# 5VAC-DC_Atmega.net
KiCad netlist of a schematic drawn in EAGLE
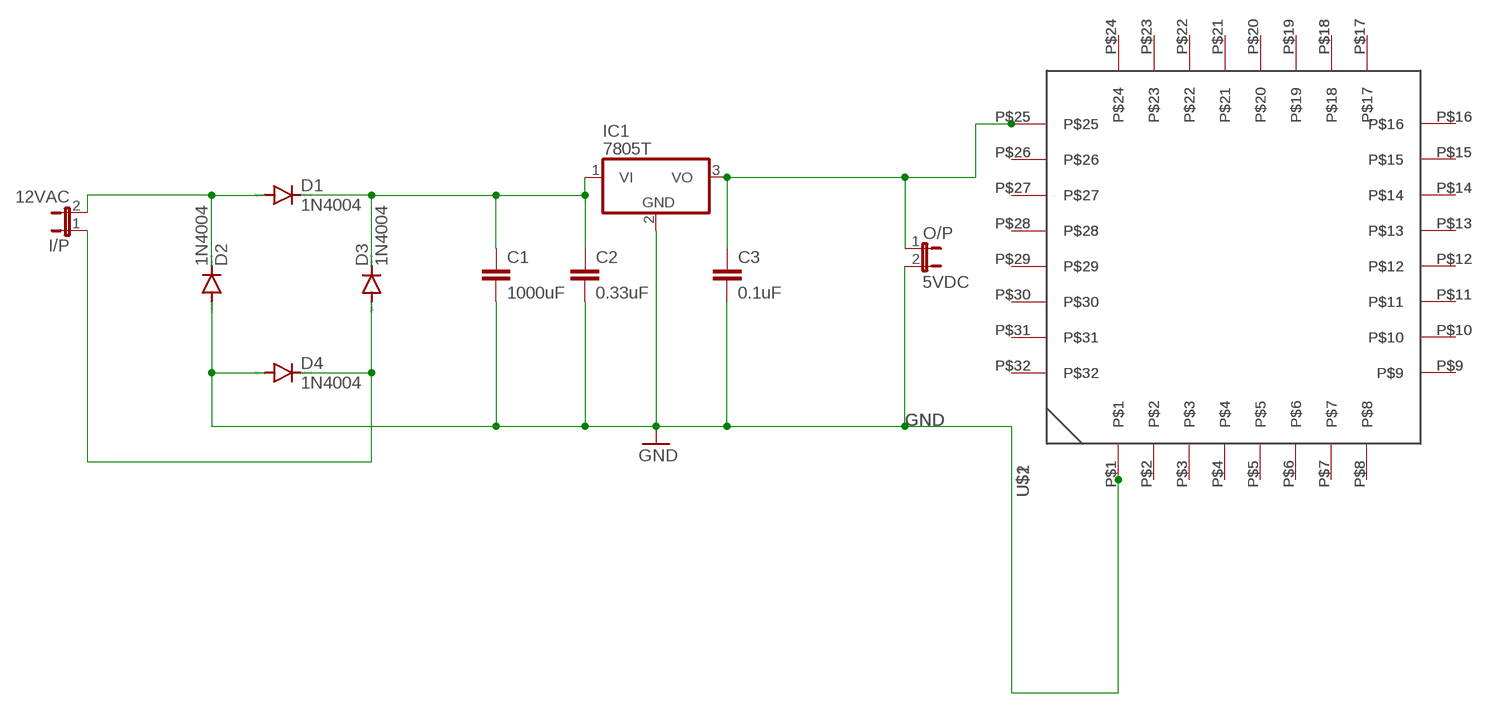
[diagram p0: schematic, sheet 1]

(export (version "E")
  (design (tool "Eeschema 10.0.6"))
  (components
    (comp (ref "C1")
      (value "1000uF")
      (footprint "eagle-import:C2.5-3")
      (libsource (lib "eagle-import") (part "C2,5-3"))
    )
    (comp (ref "C2")
      (value "0.33uF")
      (footprint "eagle-import:C2.5-3")
      (libsource (lib "eagle-import") (part "C2,5-3"))
    )
    (comp (ref "C3")
      (value "0.1uF")
      (footprint "eagle-import:C2.5-3")
      (libsource (lib "eagle-import") (part "C2,5-3"))
    )
    (comp (ref "D1")
      (value "1N4004")
      (footprint "eagle-import:DO41-10")
      (libsource (lib "eagle-import") (part "1N4004"))
    )
    (comp (ref "D2")
      (value "1N4004")
      (footprint "eagle-import:DO41-10")
      (libsource (lib "eagle-import") (part "1N4004"))
    )
    (comp (ref "D3")
      (value "1N4004")
      (footprint "eagle-import:DO41-10")
      (libsource (lib "eagle-import") (part "1N4004"))
    )
    (comp (ref "D4")
      (value "1N4004")
      (footprint "eagle-import:DO41-10")
      (libsource (lib "eagle-import") (part "1N4004"))
    )
    (comp (ref "I/P")
      (value "12VAC")
      (footprint "eagle-import:JP1")
      (libsource (lib "eagle-import") (part "JP1E"))
    )
    (comp (ref "IC1")
      (value "7805T")
      (footprint "eagle-import:TO220H")
      (libsource (lib "eagle-import") (part "78T05"))
    )
    (comp (ref "O/P")
      (value "5VDC")
      (footprint "eagle-import:JP1")
      (libsource (lib "eagle-import") (part "JP1E"))
    )
    (comp (ref "U$1")
      (value "MEGA8L-DEV")
      (footprint "eagle-import:TQFP-MEGA8L")
      (libsource (lib "eagle-import") (part "MEGA8L-DEV"))
    )
    (comp (ref "U$2")
      (value "MEGA8L-DEV")
      (footprint "eagle-import:TQFP-MEGA8L")
      (libsource (lib "eagle-import") (part "MEGA8L-DEV"))
    )
  )
  (nets
    (net (code "1") (name "GND") (class "Default")
      (node (ref "C1") (pin "2") (pinfunction "2_2") (pintype "passive"))
      (node (ref "C2") (pin "2") (pinfunction "2_2") (pintype "passive"))
      (node (ref "C3") (pin "2") (pinfunction "2_2") (pintype "passive"))
      (node (ref "D2") (pin "A") (pinfunction "A_A") (pintype "passive"))
      (node (ref "D4") (pin "A") (pinfunction "A_A") (pintype "passive"))
      (node (ref "IC1") (pin "2") (pinfunction "GND_2") (pintype "passive"))
      (node (ref "O/P") (pin "2") (pinfunction "2_2") (pintype "passive"))
      (node (ref "U$1") (pin "P$1") (pinfunction "P$1_P$1") (pintype "bidirectional"))
      (node (ref "U$2") (pin "P$1") (pinfunction "P$1_P$1") (pintype "bidirectional"))
    )
    (net (code "2") (name "Net-(D1-PadA)") (class "Default")
      (node (ref "D1") (pin "A") (pinfunction "A_A") (pintype "passive"))
      (node (ref "D2") (pin "C") (pinfunction "C_C") (pintype "passive"))
      (node (ref "I/P") (pin "2") (pinfunction "2_2") (pintype "passive"))
    )
    (net (code "3") (name "Net-(D3-PadA)") (class "Default")
      (node (ref "D3") (pin "A") (pinfunction "A_A") (pintype "passive"))
      (node (ref "D4") (pin "C") (pinfunction "C_C") (pintype "passive"))
      (node (ref "I/P") (pin "1") (pinfunction "1_1") (pintype "passive"))
    )
    (net (code "4") (name "Net-(IC1-VI)") (class "Default")
      (node (ref "C1") (pin "1") (pinfunction "1_1") (pintype "passive"))
      (node (ref "C2") (pin "1") (pinfunction "1_1") (pintype "passive"))
      (node (ref "D1") (pin "C") (pinfunction "C_C") (pintype "passive"))
      (node (ref "D3") (pin "C") (pinfunction "C_C") (pintype "passive"))
      (node (ref "IC1") (pin "1") (pinfunction "VI_1") (pintype "input"))
    )
    (net (code "5") (name "Net-(IC1-VO)") (class "Default")
      (node (ref "C3") (pin "1") (pinfunction "1_1") (pintype "passive"))
      (node (ref "IC1") (pin "3") (pinfunction "VO_3") (pintype "passive"))
      (node (ref "O/P") (pin "1") (pinfunction "1_1") (pintype "passive"))
      (node (ref "U$1") (pin "P$25") (pinfunction "P$25_P$25") (pintype "bidirectional"))
      (node (ref "U$2") (pin "P$25") (pinfunction "P$25_P$25") (pintype "bidirectional"))
    )
    (net (code "6") (name "Net-(U$1-PadP$2)") (class "Default")
      (node (ref "U$1") (pin "P$2") (pinfunction "P$2_P$2") (pintype "bidirectional"))
      (node (ref "U$2") (pin "P$2") (pinfunction "P$2_P$2") (pintype "bidirectional"))
    )
    (net (code "7") (name "Net-(U$1-PadP$3)") (class "Default")
      (node (ref "U$1") (pin "P$3") (pinfunction "P$3_P$3") (pintype "bidirectional"))
      (node (ref "U$2") (pin "P$3") (pinfunction "P$3_P$3") (pintype "bidirectional"))
    )
    (net (code "8") (name "Net-(U$1-PadP$4)") (class "Default")
      (node (ref "U$1") (pin "P$4") (pinfunction "P$4_P$4") (pintype "bidirectional"))
      (node (ref "U$2") (pin "P$4") (pinfunction "P$4_P$4") (pintype "bidirectional"))
    )
    (net (code "9") (name "Net-(U$1-PadP$5)") (class "Default")
      (node (ref "U$1") (pin "P$5") (pinfunction "P$5_P$5") (pintype "bidirectional"))
      (node (ref "U$2") (pin "P$5") (pinfunction "P$5_P$5") (pintype "bidirectional"))
    )
    (net (code "10") (name "Net-(U$1-PadP$6)") (class "Default")
      (node (ref "U$1") (pin "P$6") (pinfunction "P$6_P$6") (pintype "bidirectional"))
      (node (ref "U$2") (pin "P$6") (pinfunction "P$6_P$6") (pintype "bidirectional"))
    )
    (net (code "11") (name "Net-(U$1-PadP$7)") (class "Default")
      (node (ref "U$1") (pin "P$7") (pinfunction "P$7_P$7") (pintype "bidirectional"))
      (node (ref "U$2") (pin "P$7") (pinfunction "P$7_P$7") (pintype "bidirectional"))
    )
    (net (code "12") (name "Net-(U$1-PadP$8)") (class "Default")
      (node (ref "U$1") (pin "P$8") (pinfunction "P$8_P$8") (pintype "bidirectional"))
      (node (ref "U$2") (pin "P$8") (pinfunction "P$8_P$8") (pintype "bidirectional"))
    )
    (net (code "13") (name "Net-(U$1-PadP$9)") (class "Default")
      (node (ref "U$1") (pin "P$9") (pinfunction "P$9_P$9") (pintype "bidirectional"))
      (node (ref "U$2") (pin "P$9") (pinfunction "P$9_P$9") (pintype "bidirectional"))
    )
    (net (code "14") (name "Net-(U$1-PadP$10)") (class "Default")
      (node (ref "U$1") (pin "P$10") (pinfunction "P$10_P$10") (pintype "bidirectional"))
      (node (ref "U$2") (pin "P$10") (pinfunction "P$10_P$10") (pintype "bidirectional"))
    )
    (net (code "15") (name "Net-(U$1-PadP$11)") (class "Default")
      (node (ref "U$1") (pin "P$11") (pinfunction "P$11_P$11") (pintype "bidirectional"))
      (node (ref "U$2") (pin "P$11") (pinfunction "P$11_P$11") (pintype "bidirectional"))
    )
    (net (code "16") (name "Net-(U$1-PadP$12)") (class "Default")
      (node (ref "U$1") (pin "P$12") (pinfunction "P$12_P$12") (pintype "bidirectional"))
      (node (ref "U$2") (pin "P$12") (pinfunction "P$12_P$12") (pintype "bidirectional"))
    )
    (net (code "17") (name "Net-(U$1-PadP$13)") (class "Default")
      (node (ref "U$1") (pin "P$13") (pinfunction "P$13_P$13") (pintype "bidirectional"))
      (node (ref "U$2") (pin "P$13") (pinfunction "P$13_P$13") (pintype "bidirectional"))
    )
    (net (code "18") (name "Net-(U$1-PadP$14)") (class "Default")
      (node (ref "U$1") (pin "P$14") (pinfunction "P$14_P$14") (pintype "bidirectional"))
      (node (ref "U$2") (pin "P$14") (pinfunction "P$14_P$14") (pintype "bidirectional"))
    )
    (net (code "19") (name "Net-(U$1-PadP$15)") (class "Default")
      (node (ref "U$1") (pin "P$15") (pinfunction "P$15_P$15") (pintype "bidirectional"))
      (node (ref "U$2") (pin "P$15") (pinfunction "P$15_P$15") (pintype "bidirectional"))
    )
    (net (code "20") (name "Net-(U$1-PadP$16)") (class "Default")
      (node (ref "U$1") (pin "P$16") (pinfunction "P$16_P$16") (pintype "bidirectional"))
      (node (ref "U$2") (pin "P$16") (pinfunction "P$16_P$16") (pintype "bidirectional"))
    )
    (net (code "21") (name "Net-(U$1-PadP$17)") (class "Default")
      (node (ref "U$1") (pin "P$17") (pinfunction "P$17_P$17") (pintype "bidirectional"))
      (node (ref "U$2") (pin "P$17") (pinfunction "P$17_P$17") (pintype "bidirectional"))
    )
    (net (code "22") (name "Net-(U$1-PadP$18)") (class "Default")
      (node (ref "U$1") (pin "P$18") (pinfunction "P$18_P$18") (pintype "bidirectional"))
      (node (ref "U$2") (pin "P$18") (pinfunction "P$18_P$18") (pintype "bidirectional"))
    )
    (net (code "23") (name "Net-(U$1-PadP$19)") (class "Default")
      (node (ref "U$1") (pin "P$19") (pinfunction "P$19_P$19") (pintype "bidirectional"))
      (node (ref "U$2") (pin "P$19") (pinfunction "P$19_P$19") (pintype "bidirectional"))
    )
    (net (code "24") (name "Net-(U$1-PadP$20)") (class "Default")
      (node (ref "U$1") (pin "P$20") (pinfunction "P$20_P$20") (pintype "bidirectional"))
      (node (ref "U$2") (pin "P$20") (pinfunction "P$20_P$20") (pintype "bidirectional"))
    )
    (net (code "25") (name "Net-(U$1-PadP$21)") (class "Default")
      (node (ref "U$1") (pin "P$21") (pinfunction "P$21_P$21") (pintype "bidirectional"))
      (node (ref "U$2") (pin "P$21") (pinfunction "P$21_P$21") (pintype "bidirectional"))
    )
    (net (code "26") (name "Net-(U$1-PadP$22)") (class "Default")
      (node (ref "U$1") (pin "P$22") (pinfunction "P$22_P$22") (pintype "bidirectional"))
      (node (ref "U$2") (pin "P$22") (pinfunction "P$22_P$22") (pintype "bidirectional"))
    )
    (net (code "27") (name "Net-(U$1-PadP$23)") (class "Default")
      (node (ref "U$1") (pin "P$23") (pinfunction "P$23_P$23") (pintype "bidirectional"))
      (node (ref "U$2") (pin "P$23") (pinfunction "P$23_P$23") (pintype "bidirectional"))
    )
    (net (code "28") (name "Net-(U$1-PadP$24)") (class "Default")
      (node (ref "U$1") (pin "P$24") (pinfunction "P$24_P$24") (pintype "bidirectional"))
      (node (ref "U$2") (pin "P$24") (pinfunction "P$24_P$24") (pintype "bidirectional"))
    )
    (net (code "29") (name "Net-(U$1-PadP$26)") (class "Default")
      (node (ref "U$1") (pin "P$26") (pinfunction "P$26_P$26") (pintype "bidirectional"))
      (node (ref "U$2") (pin "P$26") (pinfunction "P$26_P$26") (pintype "bidirectional"))
    )
    (net (code "30") (name "Net-(U$1-PadP$27)") (class "Default")
      (node (ref "U$1") (pin "P$27") (pinfunction "P$27_P$27") (pintype "bidirectional"))
      (node (ref "U$2") (pin "P$27") (pinfunction "P$27_P$27") (pintype "bidirectional"))
    )
    (net (code "31") (name "Net-(U$1-PadP$28)") (class "Default")
      (node (ref "U$1") (pin "P$28") (pinfunction "P$28_P$28") (pintype "bidirectional"))
      (node (ref "U$2") (pin "P$28") (pinfunction "P$28_P$28") (pintype "bidirectional"))
    )
    (net (code "32") (name "Net-(U$1-PadP$29)") (class "Default")
      (node (ref "U$1") (pin "P$29") (pinfunction "P$29_P$29") (pintype "bidirectional"))
      (node (ref "U$2") (pin "P$29") (pinfunction "P$29_P$29") (pintype "bidirectional"))
    )
    (net (code "33") (name "Net-(U$1-PadP$30)") (class "Default")
      (node (ref "U$1") (pin "P$30") (pinfunction "P$30_P$30") (pintype "bidirectional"))
      (node (ref "U$2") (pin "P$30") (pinfunction "P$30_P$30") (pintype "bidirectional"))
    )
    (net (code "34") (name "Net-(U$1-PadP$31)") (class "Default")
      (node (ref "U$1") (pin "P$31") (pinfunction "P$31_P$31") (pintype "bidirectional"))
      (node (ref "U$2") (pin "P$31") (pinfunction "P$31_P$31") (pintype "bidirectional"))
    )
    (net (code "35") (name "Net-(U$1-PadP$32)") (class "Default")
      (node (ref "U$1") (pin "P$32") (pinfunction "P$32_P$32") (pintype "bidirectional"))
      (node (ref "U$2") (pin "P$32") (pinfunction "P$32_P$32") (pintype "bidirectional"))
    )
  )
)
